# Power_Distro_Board_V4.net
KiCad netlist of a schematic drawn in EAGLE
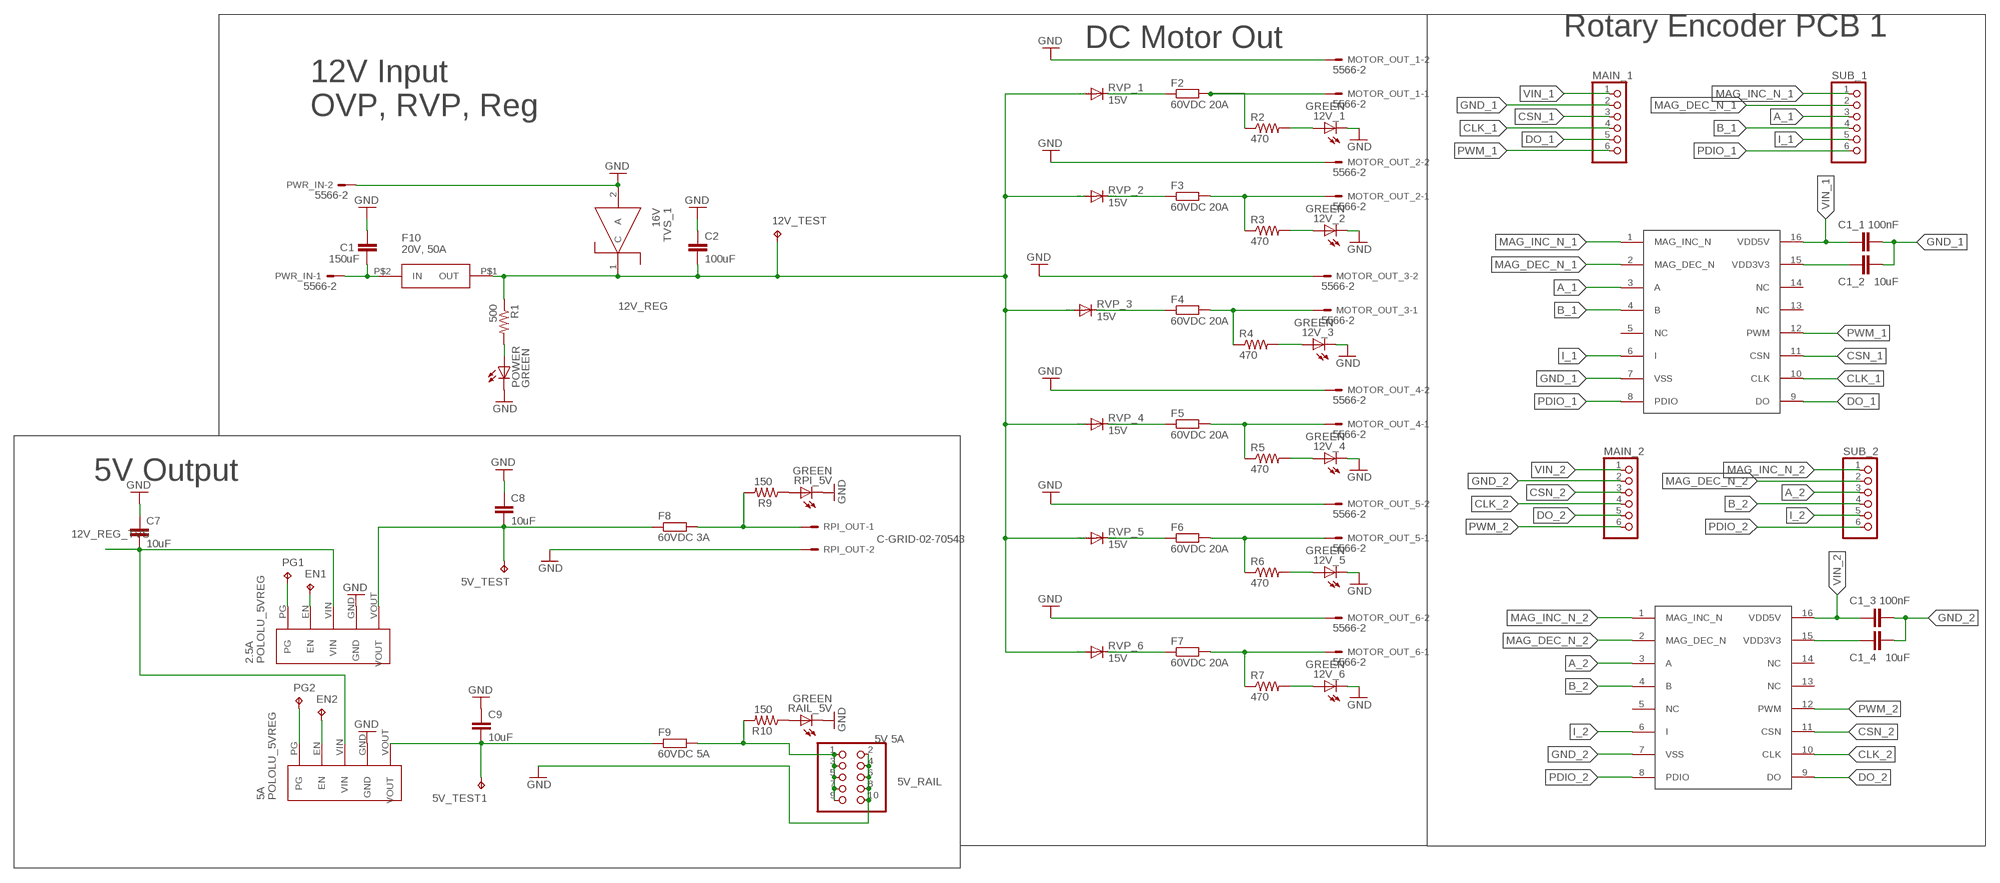
[diagram p0: schematic, sheet 1]

(export (version "E")
  (design (tool "Eeschema 10.0.6"))
  (components
    (comp (ref "2.5A")
      (value "POLOLU_5VREG")
      (footprint "eagle-import:SIP5")
      (libsource (lib "eagle-import") (part "POLOLU_5VREG"))
    )
    (comp (ref "5A")
      (value "POLOLU_5VREG")
      (footprint "eagle-import:SIP5")
      (libsource (lib "eagle-import") (part "POLOLU_5VREG"))
    )
    (comp (ref "5V_RAIL")
      (value "5V 5A")
      (footprint "eagle-import:2X05")
      (libsource (lib "eagle-import") (part "PINHD-2X5"))
    )
    (comp (ref "5V_TEST")
      (value "TPPAD1-13")
      (footprint "eagle-import:P1-13")
      (libsource (lib "eagle-import") (part "TPPAD1-13"))
    )
    (comp (ref "5V_TEST1")
      (value "TPPAD1-13")
      (footprint "eagle-import:P1-13")
      (libsource (lib "eagle-import") (part "TPPAD1-13"))
    )
    (comp (ref "12V_1")
      (value "GREEN")
      (footprint "eagle-import:SML1206")
      (libsource (lib "eagle-import") (part "LEDSML1206"))
    )
    (comp (ref "12V_2")
      (value "GREEN")
      (footprint "eagle-import:SML1206")
      (libsource (lib "eagle-import") (part "LEDSML1206"))
    )
    (comp (ref "12V_3")
      (value "GREEN")
      (footprint "eagle-import:SML1206")
      (libsource (lib "eagle-import") (part "LEDSML1206"))
    )
    (comp (ref "12V_4")
      (value "GREEN")
      (footprint "eagle-import:SML1206")
      (libsource (lib "eagle-import") (part "LEDSML1206"))
    )
    (comp (ref "12V_5")
      (value "GREEN")
      (footprint "eagle-import:SML1206")
      (libsource (lib "eagle-import") (part "LEDSML1206"))
    )
    (comp (ref "12V_6")
      (value "GREEN")
      (footprint "eagle-import:SML1206")
      (libsource (lib "eagle-import") (part "LEDSML1206"))
    )
    (comp (ref "12V_TEST")
      (value "TPPAD1-13")
      (footprint "eagle-import:P1-13")
      (libsource (lib "eagle-import") (part "TPPAD1-13"))
    )
    (comp (ref "C1")
      (value "150uF")
      (footprint "eagle-import:C1206")
      (libsource (lib "eagle-import") (part "C-EUC1206"))
    )
    (comp (ref "C1_1")
      (value "100nF")
      (footprint "eagle-import:C1206")
      (libsource (lib "eagle-import") (part "C-EUC1206"))
    )
    (comp (ref "C1_2")
      (value "10uF")
      (footprint "eagle-import:C1206")
      (libsource (lib "eagle-import") (part "C-EUC1206"))
    )
    (comp (ref "C1_3")
      (value "100nF")
      (footprint "eagle-import:C1206")
      (libsource (lib "eagle-import") (part "C-EUC1206"))
    )
    (comp (ref "C1_4")
      (value "10uF")
      (footprint "eagle-import:C1206")
      (libsource (lib "eagle-import") (part "C-EUC1206"))
    )
    (comp (ref "C2")
      (value "100uF")
      (footprint "eagle-import:C1206")
      (libsource (lib "eagle-import") (part "C-EUC1206"))
    )
    (comp (ref "C7")
      (value "10uF")
      (footprint "eagle-import:C1206")
      (libsource (lib "eagle-import") (part "C-EUC1206"))
    )
    (comp (ref "C8")
      (value "10uF")
      (footprint "eagle-import:C1206")
      (libsource (lib "eagle-import") (part "C-EUC1206"))
    )
    (comp (ref "C9")
      (value "10uF")
      (footprint "eagle-import:C1206")
      (libsource (lib "eagle-import") (part "C-EUC1206"))
    )
    (comp (ref "EN1")
      (value "TPPAD1-13")
      (footprint "eagle-import:P1-13")
      (libsource (lib "eagle-import") (part "TPPAD1-13"))
    )
    (comp (ref "EN2")
      (value "TPPAD1-13")
      (footprint "eagle-import:P1-13")
      (libsource (lib "eagle-import") (part "TPPAD1-13"))
    )
    (comp (ref "ENC_1")
      (value "ENCODER_AS5045B")
      (footprint "eagle-import:SSOP16")
      (libsource (lib "eagle-import") (part "ENCODER_AS5045B"))
    )
    (comp (ref "ENC_2")
      (value "ENCODER_AS5045B")
      (footprint "eagle-import:SSOP16")
      (libsource (lib "eagle-import") (part "ENCODER_AS5045B"))
    )
    (comp (ref "F2")
      (value "60VDC 20A")
      (footprint "eagle-import:M1206")
      (libsource (lib "eagle-import") (part "R-EU_M1206"))
    )
    (comp (ref "F3")
      (value "60VDC 20A")
      (footprint "eagle-import:M1206")
      (libsource (lib "eagle-import") (part "R-EU_M1206"))
    )
    (comp (ref "F4")
      (value "60VDC 20A")
      (footprint "eagle-import:M1206")
      (libsource (lib "eagle-import") (part "R-EU_M1206"))
    )
    (comp (ref "F5")
      (value "60VDC 20A")
      (footprint "eagle-import:M1206")
      (libsource (lib "eagle-import") (part "R-EU_M1206"))
    )
    (comp (ref "F6")
      (value "60VDC 20A")
      (footprint "eagle-import:M1206")
      (libsource (lib "eagle-import") (part "R-EU_M1206"))
    )
    (comp (ref "F7")
      (value "60VDC 20A")
      (footprint "eagle-import:M1206")
      (libsource (lib "eagle-import") (part "R-EU_M1206"))
    )
    (comp (ref "F8")
      (value "60VDC 3A")
      (footprint "eagle-import:M1206")
      (libsource (lib "eagle-import") (part "R-EU_M1206"))
    )
    (comp (ref "F9")
      (value "60VDC 5A")
      (footprint "eagle-import:M1206")
      (libsource (lib "eagle-import") (part "R-EU_M1206"))
    )
    (comp (ref "F10")
      (value "20V, 50A")
      (footprint "eagle-import:NANO")
      (libsource (lib "eagle-import") (part "LITTLEFUSE_NANO"))
    )
    (comp (ref "MAIN_1")
      (value "PINHD-1X6")
      (footprint "eagle-import:1X06")
      (libsource (lib "eagle-import") (part "PINHD-1X6"))
    )
    (comp (ref "MAIN_2")
      (value "PINHD-1X6")
      (footprint "eagle-import:1X06")
      (libsource (lib "eagle-import") (part "PINHD-1X6"))
    )
    (comp (ref "MOTOR_OUT_1")
      (value "5566-2")
      (footprint "eagle-import:5566-2")
      (libsource (lib "eagle-import") (part "5566-2"))
    )
    (comp (ref "MOTOR_OUT_2")
      (value "5566-2")
      (footprint "eagle-import:5566-2")
      (libsource (lib "eagle-import") (part "5566-2"))
    )
    (comp (ref "MOTOR_OUT_3")
      (value "5566-2")
      (footprint "eagle-import:5566-2")
      (libsource (lib "eagle-import") (part "5566-2"))
    )
    (comp (ref "MOTOR_OUT_4")
      (value "5566-2")
      (footprint "eagle-import:5566-2")
      (libsource (lib "eagle-import") (part "5566-2"))
    )
    (comp (ref "MOTOR_OUT_5")
      (value "5566-2")
      (footprint "eagle-import:5566-2")
      (libsource (lib "eagle-import") (part "5566-2"))
    )
    (comp (ref "MOTOR_OUT_6")
      (value "5566-2")
      (footprint "eagle-import:5566-2")
      (libsource (lib "eagle-import") (part "5566-2"))
    )
    (comp (ref "PG1")
      (value "TPPAD1-13")
      (footprint "eagle-import:P1-13")
      (libsource (lib "eagle-import") (part "TPPAD1-13"))
    )
    (comp (ref "PG2")
      (value "TPPAD1-13")
      (footprint "eagle-import:P1-13")
      (libsource (lib "eagle-import") (part "TPPAD1-13"))
    )
    (comp (ref "POWER")
      (value "GREEN")
      (footprint "eagle-import:SML1206")
      (libsource (lib "eagle-import") (part "LEDSML1206"))
    )
    (comp (ref "PWR_IN")
      (value "5566-2")
      (footprint "eagle-import:5566-2")
      (libsource (lib "eagle-import") (part "5566-2"))
    )
    (comp (ref "R1")
      (value "500")
      (footprint "eagle-import:R1206")
      (libsource (lib "eagle-import") (part "R-US_R1206"))
    )
    (comp (ref "R2")
      (value "470")
      (footprint "eagle-import:R1206")
      (libsource (lib "eagle-import") (part "R-US_R1206"))
    )
    (comp (ref "R3")
      (value "470")
      (footprint "eagle-import:R1206")
      (libsource (lib "eagle-import") (part "R-US_R1206"))
    )
    (comp (ref "R4")
      (value "470")
      (footprint "eagle-import:R1206")
      (libsource (lib "eagle-import") (part "R-US_R1206"))
    )
    (comp (ref "R5")
      (value "470")
      (footprint "eagle-import:R1206")
      (libsource (lib "eagle-import") (part "R-US_R1206"))
    )
    (comp (ref "R6")
      (value "470")
      (footprint "eagle-import:R1206")
      (libsource (lib "eagle-import") (part "R-US_R1206"))
    )
    (comp (ref "R7")
      (value "470")
      (footprint "eagle-import:R1206")
      (libsource (lib "eagle-import") (part "R-US_R1206"))
    )
    (comp (ref "R9")
      (value "150")
      (footprint "eagle-import:R1206")
      (libsource (lib "eagle-import") (part "R-US_R1206"))
    )
    (comp (ref "R10")
      (value "150")
      (footprint "eagle-import:R1206")
      (libsource (lib "eagle-import") (part "R-US_R1206"))
    )
    (comp (ref "RAIL_5V")
      (value "GREEN")
      (footprint "eagle-import:SML1206")
      (libsource (lib "eagle-import") (part "LEDSML1206"))
    )
    (comp (ref "RPI_5V")
      (value "GREEN")
      (footprint "eagle-import:SML1206")
      (libsource (lib "eagle-import") (part "LEDSML1206"))
    )
    (comp (ref "RPI_OUT")
      (value "C-GRID-02-70543")
      (footprint "eagle-import:70543-02")
      (libsource (lib "eagle-import") (part "C-GRID-02-70543"))
    )
    (comp (ref "RVP_1")
      (value "15V")
      (footprint "eagle-import:TO220ACS")
      (libsource (lib "eagle-import") (part "BYT08P"))
    )
    (comp (ref "RVP_2")
      (value "15V")
      (footprint "eagle-import:TO220ACS")
      (libsource (lib "eagle-import") (part "BYT08P"))
    )
    (comp (ref "RVP_3")
      (value "15V")
      (footprint "eagle-import:TO220ACS")
      (libsource (lib "eagle-import") (part "BYT08P"))
    )
    (comp (ref "RVP_4")
      (value "15V")
      (footprint "eagle-import:TO220ACS")
      (libsource (lib "eagle-import") (part "BYT08P"))
    )
    (comp (ref "RVP_5")
      (value "15V")
      (footprint "eagle-import:TO220ACS")
      (libsource (lib "eagle-import") (part "BYT08P"))
    )
    (comp (ref "RVP_6")
      (value "15V")
      (footprint "eagle-import:TO220ACS")
      (libsource (lib "eagle-import") (part "BYT08P"))
    )
    (comp (ref "SUB_1")
      (value "PINHD-1X6")
      (footprint "eagle-import:1X06")
      (libsource (lib "eagle-import") (part "PINHD-1X6"))
    )
    (comp (ref "SUB_2")
      (value "PINHD-1X6")
      (footprint "eagle-import:1X06")
      (libsource (lib "eagle-import") (part "PINHD-1X6"))
    )
    (comp (ref "TVS_1")
      (value "16V")
      (footprint "eagle-import:DO-214AC")
      (libsource (lib "eagle-import") (part "SMAJ26A_TVSSMA"))
    )
  )
  (nets
    (net (code "1") (name "/12V_REG") (class "Default")
      (node (ref "12V_TEST") (pin "TP") (pinfunction "TP_TP") (pintype "input"))
      (node (ref "C2") (pin "2") (pinfunction "2_2") (pintype "passive"))
      (node (ref "F10") (pin "P$1") (pinfunction "OUT_P$1") (pintype "bidirectional"))
      (node (ref "R1") (pin "1") (pinfunction "1_1") (pintype "passive"))
      (node (ref "RVP_1") (pin "A") (pinfunction "A_A") (pintype "passive"))
      (node (ref "RVP_2") (pin "A") (pinfunction "A_A") (pintype "passive"))
      (node (ref "RVP_3") (pin "A") (pinfunction "A_A") (pintype "passive"))
      (node (ref "RVP_4") (pin "A") (pinfunction "A_A") (pintype "passive"))
      (node (ref "RVP_5") (pin "A") (pinfunction "A_A") (pintype "passive"))
      (node (ref "RVP_6") (pin "A") (pinfunction "A_A") (pintype "passive"))
      (node (ref "TVS_1") (pin "1") (pinfunction "C_1") (pintype "bidirectional"))
    )
    (net (code "2") (name "/12V_REG_TVS") (class "Default")
      (node (ref "2.5A") (pin "VIN") (pinfunction "VIN_VIN") (pintype "bidirectional"))
      (node (ref "5A") (pin "VIN") (pinfunction "VIN_VIN") (pintype "bidirectional"))
      (node (ref "C7") (pin "2") (pinfunction "2_2") (pintype "passive"))
    )
    (net (code "3") (name "A_1") (class "Default")
      (node (ref "ENC_1") (pin "3") (pinfunction "A_3") (pintype "bidirectional"))
      (node (ref "SUB_1") (pin "3") (pinfunction "3_3") (pintype "passive"))
    )
    (net (code "4") (name "A_2") (class "Default")
      (node (ref "ENC_2") (pin "3") (pinfunction "A_3") (pintype "bidirectional"))
      (node (ref "SUB_2") (pin "3") (pinfunction "3_3") (pintype "passive"))
    )
    (net (code "5") (name "B_1") (class "Default")
      (node (ref "ENC_1") (pin "4") (pinfunction "B_4") (pintype "bidirectional"))
      (node (ref "SUB_1") (pin "4") (pinfunction "4_4") (pintype "passive"))
    )
    (net (code "6") (name "B_2") (class "Default")
      (node (ref "ENC_2") (pin "4") (pinfunction "B_4") (pintype "bidirectional"))
      (node (ref "SUB_2") (pin "4") (pinfunction "4_4") (pintype "passive"))
    )
    (net (code "7") (name "CLK_1") (class "Default")
      (node (ref "ENC_1") (pin "10") (pinfunction "CLK_10") (pintype "bidirectional"))
      (node (ref "MAIN_1") (pin "4") (pinfunction "4_4") (pintype "passive"))
    )
    (net (code "8") (name "CLK_2") (class "Default")
      (node (ref "ENC_2") (pin "10") (pinfunction "CLK_10") (pintype "bidirectional"))
      (node (ref "MAIN_2") (pin "4") (pinfunction "4_4") (pintype "passive"))
    )
    (net (code "9") (name "CSN_1") (class "Default")
      (node (ref "ENC_1") (pin "11") (pinfunction "CSN_11") (pintype "bidirectional"))
      (node (ref "MAIN_1") (pin "3") (pinfunction "3_3") (pintype "passive"))
    )
    (net (code "10") (name "CSN_2") (class "Default")
      (node (ref "ENC_2") (pin "11") (pinfunction "CSN_11") (pintype "bidirectional"))
      (node (ref "MAIN_2") (pin "3") (pinfunction "3_3") (pintype "passive"))
    )
    (net (code "11") (name "DO_1") (class "Default")
      (node (ref "ENC_1") (pin "9") (pinfunction "DO_9") (pintype "bidirectional"))
      (node (ref "MAIN_1") (pin "5") (pinfunction "5_5") (pintype "passive"))
    )
    (net (code "12") (name "DO_2") (class "Default")
      (node (ref "ENC_2") (pin "9") (pinfunction "DO_9") (pintype "bidirectional"))
      (node (ref "MAIN_2") (pin "5") (pinfunction "5_5") (pintype "passive"))
    )
    (net (code "13") (name "GND") (class "Default")
      (node (ref "12V_1") (pin "C") (pinfunction "C_C") (pintype "passive"))
      (node (ref "12V_2") (pin "C") (pinfunction "C_C") (pintype "passive"))
      (node (ref "12V_3") (pin "C") (pinfunction "C_C") (pintype "passive"))
      (node (ref "12V_4") (pin "C") (pinfunction "C_C") (pintype "passive"))
      (node (ref "12V_5") (pin "C") (pinfunction "C_C") (pintype "passive"))
      (node (ref "12V_6") (pin "C") (pinfunction "C_C") (pintype "passive"))
      (node (ref "2.5A") (pin "GND") (pinfunction "GND_GND") (pintype "bidirectional"))
      (node (ref "5A") (pin "GND") (pinfunction "GND_GND") (pintype "bidirectional"))
      (node (ref "5V_RAIL") (pin "10") (pinfunction "10_10") (pintype "passive"))
      (node (ref "5V_RAIL") (pin "2") (pinfunction "2_2") (pintype "passive"))
      (node (ref "5V_RAIL") (pin "4") (pinfunction "4_4") (pintype "passive"))
      (node (ref "5V_RAIL") (pin "6") (pinfunction "6_6") (pintype "passive"))
      (node (ref "5V_RAIL") (pin "8") (pinfunction "8_8") (pintype "passive"))
      (node (ref "C1") (pin "1") (pinfunction "1_1") (pintype "passive"))
      (node (ref "C2") (pin "1") (pinfunction "1_1") (pintype "passive"))
      (node (ref "C7") (pin "1") (pinfunction "1_1") (pintype "passive"))
      (node (ref "C8") (pin "1") (pinfunction "1_1") (pintype "passive"))
      (node (ref "C9") (pin "1") (pinfunction "1_1") (pintype "passive"))
      (node (ref "MOTOR_OUT_1") (pin "2") (pinfunction "S_2") (pintype "passive"))
      (node (ref "MOTOR_OUT_2") (pin "2") (pinfunction "S_2") (pintype "passive"))
      (node (ref "MOTOR_OUT_3") (pin "2") (pinfunction "S_2") (pintype "passive"))
      (node (ref "MOTOR_OUT_4") (pin "2") (pinfunction "S_2") (pintype "passive"))
      (node (ref "MOTOR_OUT_5") (pin "2") (pinfunction "S_2") (pintype "passive"))
      (node (ref "MOTOR_OUT_6") (pin "2") (pinfunction "S_2") (pintype "passive"))
      (node (ref "POWER") (pin "C") (pinfunction "C_C") (pintype "passive"))
      (node (ref "PWR_IN") (pin "2") (pinfunction "S_2") (pintype "passive"))
      (node (ref "RAIL_5V") (pin "C") (pinfunction "C_C") (pintype "passive"))
      (node (ref "RPI_5V") (pin "C") (pinfunction "C_C") (pintype "passive"))
      (node (ref "RPI_OUT") (pin "2") (pinfunction "S_2") (pintype "passive"))
      (node (ref "TVS_1") (pin "2") (pinfunction "A_2") (pintype "bidirectional"))
    )
    (net (code "14") (name "GND_1") (class "Default")
      (node (ref "C1_1") (pin "2") (pinfunction "2_2") (pintype "passive"))
      (node (ref "C1_2") (pin "2") (pinfunction "2_2") (pintype "passive"))
      (node (ref "ENC_1") (pin "7") (pinfunction "VSS_7") (pintype "bidirectional"))
      (node (ref "MAIN_1") (pin "2") (pinfunction "2_2") (pintype "passive"))
    )
    (net (code "15") (name "GND_2") (class "Default")
      (node (ref "C1_3") (pin "2") (pinfunction "2_2") (pintype "passive"))
      (node (ref "C1_4") (pin "2") (pinfunction "2_2") (pintype "passive"))
      (node (ref "ENC_2") (pin "7") (pinfunction "VSS_7") (pintype "bidirectional"))
      (node (ref "MAIN_2") (pin "2") (pinfunction "2_2") (pintype "passive"))
    )
    (net (code "16") (name "I_1") (class "Default")
      (node (ref "ENC_1") (pin "6") (pinfunction "I_6") (pintype "bidirectional"))
      (node (ref "SUB_1") (pin "5") (pinfunction "5_5") (pintype "passive"))
    )
    (net (code "17") (name "I_2") (class "Default")
      (node (ref "ENC_2") (pin "6") (pinfunction "I_6") (pintype "bidirectional"))
      (node (ref "SUB_2") (pin "5") (pinfunction "5_5") (pintype "passive"))
    )
    (net (code "18") (name "MAG_DEC_N_1") (class "Default")
      (node (ref "ENC_1") (pin "2") (pinfunction "MAG_DEC_N_2") (pintype "bidirectional"))
      (node (ref "SUB_1") (pin "2") (pinfunction "2_2") (pintype "passive"))
    )
    (net (code "19") (name "MAG_DEC_N_2") (class "Default")
      (node (ref "ENC_2") (pin "2") (pinfunction "MAG_DEC_N_2") (pintype "bidirectional"))
      (node (ref "SUB_2") (pin "2") (pinfunction "2_2") (pintype "passive"))
    )
    (net (code "20") (name "MAG_INC_N_1") (class "Default")
      (node (ref "ENC_1") (pin "1") (pinfunction "MAG_INC_N_1") (pintype "bidirectional"))
      (node (ref "SUB_1") (pin "1") (pinfunction "1_1") (pintype "passive"))
    )
    (net (code "21") (name "MAG_INC_N_2") (class "Default")
      (node (ref "ENC_2") (pin "1") (pinfunction "MAG_INC_N_1") (pintype "bidirectional"))
      (node (ref "SUB_2") (pin "1") (pinfunction "1_1") (pintype "passive"))
    )
    (net (code "22") (name "Net-(2.5A-PadEN)") (class "Default")
      (node (ref "2.5A") (pin "EN") (pinfunction "EN_EN") (pintype "bidirectional"))
      (node (ref "EN1") (pin "TP") (pinfunction "TP_TP") (pintype "input"))
    )
    (net (code "23") (name "Net-(2.5A-PadPG)") (class "Default")
      (node (ref "2.5A") (pin "PG") (pinfunction "PG_PG") (pintype "bidirectional"))
      (node (ref "PG1") (pin "TP") (pinfunction "TP_TP") (pintype "input"))
    )
    (net (code "24") (name "Net-(2.5A-PadVOUT)") (class "Default")
      (node (ref "2.5A") (pin "VOUT") (pinfunction "VOUT_VOUT") (pintype "bidirectional"))
      (node (ref "5V_TEST") (pin "TP") (pinfunction "TP_TP") (pintype "input"))
      (node (ref "C8") (pin "2") (pinfunction "2_2") (pintype "passive"))
      (node (ref "F8") (pin "1") (pinfunction "1_1") (pintype "passive"))
    )
    (net (code "25") (name "Net-(5A-PadEN)") (class "Default")
      (node (ref "5A") (pin "EN") (pinfunction "EN_EN") (pintype "bidirectional"))
      (node (ref "EN2") (pin "TP") (pinfunction "TP_TP") (pintype "input"))
    )
    (net (code "26") (name "Net-(5A-PadPG)") (class "Default")
      (node (ref "5A") (pin "PG") (pinfunction "PG_PG") (pintype "bidirectional"))
      (node (ref "PG2") (pin "TP") (pinfunction "TP_TP") (pintype "input"))
    )
    (net (code "27") (name "Net-(5A-PadVOUT)") (class "Default")
      (node (ref "5A") (pin "VOUT") (pinfunction "VOUT_VOUT") (pintype "bidirectional"))
      (node (ref "5V_TEST1") (pin "TP") (pinfunction "TP_TP") (pintype "input"))
      (node (ref "C9") (pin "2") (pinfunction "2_2") (pintype "passive"))
      (node (ref "F9") (pin "1") (pinfunction "1_1") (pintype "passive"))
    )
    (net (code "28") (name "Net-(5V_RAIL-Pad1)") (class "Default")
      (node (ref "5V_RAIL") (pin "1") (pinfunction "1_1") (pintype "passive"))
      (node (ref "5V_RAIL") (pin "3") (pinfunction "3_3") (pintype "passive"))
      (node (ref "5V_RAIL") (pin "5") (pinfunction "5_5") (pintype "passive"))
      (node (ref "5V_RAIL") (pin "7") (pinfunction "7_7") (pintype "passive"))
      (node (ref "5V_RAIL") (pin "9") (pinfunction "9_9") (pintype "passive"))
      (node (ref "F9") (pin "2") (pinfunction "2_2") (pintype "passive"))
      (node (ref "R10") (pin "2") (pinfunction "2_2") (pintype "passive"))
    )
    (net (code "29") (name "Net-(12V_1-PadA)") (class "Default")
      (node (ref "12V_1") (pin "A") (pinfunction "A_A") (pintype "passive"))
      (node (ref "R2") (pin "2") (pinfunction "2_2") (pintype "passive"))
    )
    (net (code "30") (name "Net-(12V_2-PadA)") (class "Default")
      (node (ref "12V_2") (pin "A") (pinfunction "A_A") (pintype "passive"))
      (node (ref "R3") (pin "2") (pinfunction "2_2") (pintype "passive"))
    )
    (net (code "31") (name "Net-(12V_3-PadA)") (class "Default")
      (node (ref "12V_3") (pin "A") (pinfunction "A_A") (pintype "passive"))
      (node (ref "R4") (pin "2") (pinfunction "2_2") (pintype "passive"))
    )
    (net (code "32") (name "Net-(12V_4-PadA)") (class "Default")
      (node (ref "12V_4") (pin "A") (pinfunction "A_A") (pintype "passive"))
      (node (ref "R5") (pin "2") (pinfunction "2_2") (pintype "passive"))
    )
    (net (code "33") (name "Net-(12V_5-PadA)") (class "Default")
      (node (ref "12V_5") (pin "A") (pinfunction "A_A") (pintype "passive"))
      (node (ref "R6") (pin "2") (pinfunction "2_2") (pintype "passive"))
    )
    (net (code "34") (name "Net-(12V_6-PadA)") (class "Default")
      (node (ref "12V_6") (pin "A") (pinfunction "A_A") (pintype "passive"))
      (node (ref "R7") (pin "2") (pinfunction "2_2") (pintype "passive"))
    )
    (net (code "35") (name "Net-(ENC_1-VDD3V3)") (class "Default")
      (node (ref "C1_2") (pin "1") (pinfunction "1_1") (pintype "passive"))
      (node (ref "ENC_1") (pin "15") (pinfunction "VDD3V3_15") (pintype "bidirectional"))
    )
    (net (code "36") (name "Net-(ENC_2-VDD3V3)") (class "Default")
      (node (ref "C1_4") (pin "1") (pinfunction "1_1") (pintype "passive"))
      (node (ref "ENC_2") (pin "15") (pinfunction "VDD3V3_15") (pintype "bidirectional"))
    )
    (net (code "37") (name "Net-(F2-Pad1)") (class "Default")
      (node (ref "F2") (pin "1") (pinfunction "1_1") (pintype "passive"))
      (node (ref "RVP_1") (pin "C") (pinfunction "C_C") (pintype "passive"))
    )
    (net (code "38") (name "Net-(F3-Pad1)") (class "Default")
      (node (ref "F3") (pin "1") (pinfunction "1_1") (pintype "passive"))
      (node (ref "RVP_2") (pin "C") (pinfunction "C_C") (pintype "passive"))
    )
    (net (code "39") (name "Net-(F4-Pad1)") (class "Default")
      (node (ref "F4") (pin "1") (pinfunction "1_1") (pintype "passive"))
      (node (ref "RVP_3") (pin "C") (pinfunction "C_C") (pintype "passive"))
    )
    (net (code "40") (name "Net-(F5-Pad1)") (class "Default")
      (node (ref "F5") (pin "1") (pinfunction "1_1") (pintype "passive"))
      (node (ref "RVP_4") (pin "C") (pinfunction "C_C") (pintype "passive"))
    )
    (net (code "41") (name "Net-(F6-Pad1)") (class "Default")
      (node (ref "F6") (pin "1") (pinfunction "1_1") (pintype "passive"))
      (node (ref "RVP_5") (pin "C") (pinfunction "C_C") (pintype "passive"))
    )
    (net (code "42") (name "Net-(F7-Pad1)") (class "Default")
      (node (ref "F7") (pin "1") (pinfunction "1_1") (pintype "passive"))
      (node (ref "RVP_6") (pin "C") (pinfunction "C_C") (pintype "passive"))
    )
    (net (code "43") (name "Net-(F10-IN)") (class "Default")
      (node (ref "C1") (pin "2") (pinfunction "2_2") (pintype "passive"))
      (node (ref "F10") (pin "P$2") (pinfunction "IN_P$2") (pintype "bidirectional"))
      (node (ref "PWR_IN") (pin "1") (pinfunction "S_1") (pintype "passive"))
    )
    (net (code "44") (name "Net-(MOTOR_OUT_1A-S)") (class "Default")
      (node (ref "F2") (pin "2") (pinfunction "2_2") (pintype "passive"))
      (node (ref "MOTOR_OUT_1") (pin "1") (pinfunction "S_1") (pintype "passive"))
      (node (ref "R2") (pin "1") (pinfunction "1_1") (pintype "passive"))
    )
    (net (code "45") (name "Net-(MOTOR_OUT_2A-S)") (class "Default")
      (node (ref "F3") (pin "2") (pinfunction "2_2") (pintype "passive"))
      (node (ref "MOTOR_OUT_2") (pin "1") (pinfunction "S_1") (pintype "passive"))
      (node (ref "R3") (pin "1") (pinfunction "1_1") (pintype "passive"))
    )
    (net (code "46") (name "Net-(MOTOR_OUT_3A-S)") (class "Default")
      (node (ref "F4") (pin "2") (pinfunction "2_2") (pintype "passive"))
      (node (ref "MOTOR_OUT_3") (pin "1") (pinfunction "S_1") (pintype "passive"))
      (node (ref "R4") (pin "1") (pinfunction "1_1") (pintype "passive"))
    )
    (net (code "47") (name "Net-(MOTOR_OUT_4A-S)") (class "Default")
      (node (ref "F5") (pin "2") (pinfunction "2_2") (pintype "passive"))
      (node (ref "MOTOR_OUT_4") (pin "1") (pinfunction "S_1") (pintype "passive"))
      (node (ref "R5") (pin "1") (pinfunction "1_1") (pintype "passive"))
    )
    (net (code "48") (name "Net-(MOTOR_OUT_5A-S)") (class "Default")
      (node (ref "F6") (pin "2") (pinfunction "2_2") (pintype "passive"))
      (node (ref "MOTOR_OUT_5") (pin "1") (pinfunction "S_1") (pintype "passive"))
      (node (ref "R6") (pin "1") (pinfunction "1_1") (pintype "passive"))
    )
    (net (code "49") (name "Net-(MOTOR_OUT_6A-S)") (class "Default")
      (node (ref "F7") (pin "2") (pinfunction "2_2") (pintype "passive"))
      (node (ref "MOTOR_OUT_6") (pin "1") (pinfunction "S_1") (pintype "passive"))
      (node (ref "R7") (pin "1") (pinfunction "1_1") (pintype "passive"))
    )
    (net (code "50") (name "Net-(POWER-PadA)") (class "Default")
      (node (ref "POWER") (pin "A") (pinfunction "A_A") (pintype "passive"))
      (node (ref "R1") (pin "2") (pinfunction "2_2") (pintype "passive"))
    )
    (net (code "51") (name "Net-(R9-Pad1)") (class "Default")
      (node (ref "R9") (pin "1") (pinfunction "1_1") (pintype "passive"))
      (node (ref "RPI_5V") (pin "A") (pinfunction "A_A") (pintype "passive"))
    )
    (net (code "52") (name "Net-(R10-Pad1)") (class "Default")
      (node (ref "R10") (pin "1") (pinfunction "1_1") (pintype "passive"))
      (node (ref "RAIL_5V") (pin "A") (pinfunction "A_A") (pintype "passive"))
    )
    (net (code "53") (name "Net-(RPI_OUTA-S)") (class "Default")
      (node (ref "F8") (pin "2") (pinfunction "2_2") (pintype "passive"))
      (node (ref "R9") (pin "2") (pinfunction "2_2") (pintype "passive"))
      (node (ref "RPI_OUT") (pin "1") (pinfunction "S_1") (pintype "passive"))
    )
    (net (code "54") (name "PDIO_1") (class "Default")
      (node (ref "ENC_1") (pin "8") (pinfunction "PDIO_8") (pintype "bidirectional"))
      (node (ref "SUB_1") (pin "6") (pinfunction "6_6") (pintype "passive"))
    )
    (net (code "55") (name "PDIO_2") (class "Default")
      (node (ref "ENC_2") (pin "8") (pinfunction "PDIO_8") (pintype "bidirectional"))
      (node (ref "SUB_2") (pin "6") (pinfunction "6_6") (pintype "passive"))
    )
    (net (code "56") (name "PWM_1") (class "Default")
      (node (ref "ENC_1") (pin "12") (pinfunction "PWM_12") (pintype "bidirectional"))
      (node (ref "MAIN_1") (pin "6") (pinfunction "6_6") (pintype "passive"))
    )
    (net (code "57") (name "PWM_2") (class "Default")
      (node (ref "ENC_2") (pin "12") (pinfunction "PWM_12") (pintype "bidirectional"))
      (node (ref "MAIN_2") (pin "6") (pinfunction "6_6") (pintype "passive"))
    )
    (net (code "58") (name "VIN_1") (class "Default")
      (node (ref "C1_1") (pin "1") (pinfunction "1_1") (pintype "passive"))
      (node (ref "ENC_1") (pin "16") (pinfunction "VDD5V_16") (pintype "bidirectional"))
      (node (ref "MAIN_1") (pin "1") (pinfunction "1_1") (pintype "passive"))
    )
    (net (code "59") (name "VIN_2") (class "Default")
      (node (ref "C1_3") (pin "1") (pinfunction "1_1") (pintype "passive"))
      (node (ref "ENC_2") (pin "16") (pinfunction "VDD5V_16") (pintype "bidirectional"))
      (node (ref "MAIN_2") (pin "1") (pinfunction "1_1") (pintype "passive"))
    )
    (net (code "60") (name "unconnected-(ENC_1-NC-Pad5)") (class "Default")
      (node (ref "ENC_1") (pin "5") (pinfunction "NC_5") (pintype "bidirectional"))
    )
    (net (code "61") (name "unconnected-(ENC_1-NC-Pad13)") (class "Default")
      (node (ref "ENC_1") (pin "13") (pinfunction "NC_13") (pintype "bidirectional"))
    )
    (net (code "62") (name "unconnected-(ENC_1-NC-Pad14)") (class "Default")
      (node (ref "ENC_1") (pin "14") (pinfunction "NC_14") (pintype "bidirectional"))
    )
    (net (code "63") (name "unconnected-(ENC_2-NC-Pad5)") (class "Default")
      (node (ref "ENC_2") (pin "5") (pinfunction "NC_5") (pintype "bidirectional"))
    )
    (net (code "64") (name "unconnected-(ENC_2-NC-Pad13)") (class "Default")
      (node (ref "ENC_2") (pin "13") (pinfunction "NC_13") (pintype "bidirectional"))
    )
    (net (code "65") (name "unconnected-(ENC_2-NC-Pad14)") (class "Default")
      (node (ref "ENC_2") (pin "14") (pinfunction "NC_14") (pintype "bidirectional"))
    )
  )
)
